# untitled.net
KiCad netlist of a schematic drawn in EAGLE
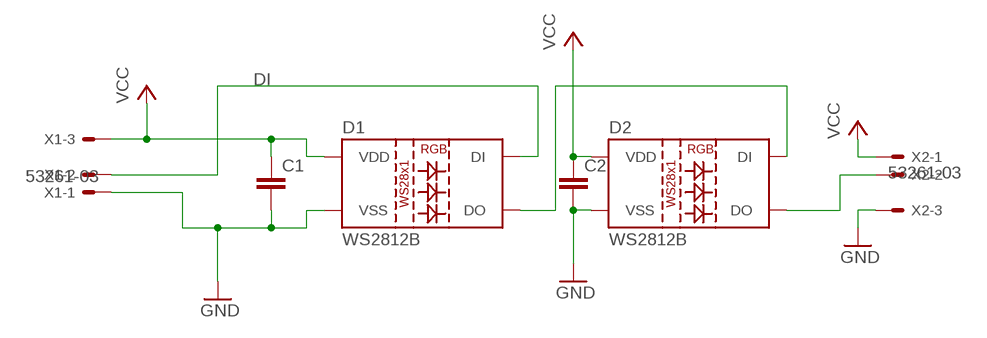
[diagram p0: schematic, sheet 1]

(export (version "E")
  (design (tool "Eeschema 10.0.6"))
  (components
    (comp (ref "C1")
      (value "C-EUC0603")
      (footprint "eagle-import:C0603")
      (libsource (lib "eagle-import") (part "C-EUC0603"))
    )
    (comp (ref "C2")
      (value "C-EUC0603")
      (footprint "eagle-import:C0603")
      (libsource (lib "eagle-import") (part "C-EUC0603"))
    )
    (comp (ref "D1")
      (value "WS2812B")
      (footprint "eagle-import:WS2812B")
      (libsource (lib "eagle-import") (part "WS2812B"))
    )
    (comp (ref "D2")
      (value "WS2812B")
      (footprint "eagle-import:WS2812B")
      (libsource (lib "eagle-import") (part "WS2812B"))
    )
    (comp (ref "X1")
      (value "53261-03")
      (footprint "eagle-import:53261-03")
      (fields (field (name "MF") "MOLEX") (field (name "MPN") "53261-0390"))
      (libsource (lib "eagle-import") (part "53?-03261"))
    )
    (comp (ref "X2")
      (value "53261-03")
      (footprint "eagle-import:53261-03")
      (fields (field (name "MF") "MOLEX") (field (name "MPN") "53261-0390"))
      (libsource (lib "eagle-import") (part "53?-03261"))
    )
  )
  (nets
    (net (code "1") (name "/DI") (class "Default")
      (node (ref "D1") (pin "4") (pinfunction "DI_4") (pintype "bidirectional"))
      (node (ref "X1") (pin "2") (pinfunction "S_2") (pintype "passive"))
    )
    (net (code "2") (name "GND") (class "Default")
      (node (ref "C1") (pin "2") (pinfunction "2_2") (pintype "passive"))
      (node (ref "C2") (pin "2") (pinfunction "2_2") (pintype "passive"))
      (node (ref "D1") (pin "3") (pinfunction "VSS_3") (pintype "bidirectional"))
      (node (ref "D2") (pin "3") (pinfunction "VSS_3") (pintype "bidirectional"))
      (node (ref "X1") (pin "1") (pinfunction "S_1") (pintype "passive"))
      (node (ref "X2") (pin "3") (pinfunction "S_3") (pintype "passive"))
    )
    (net (code "3") (name "Net-(D1-DO)") (class "Default")
      (node (ref "D1") (pin "2") (pinfunction "DO_2") (pintype "bidirectional"))
      (node (ref "D2") (pin "4") (pinfunction "DI_4") (pintype "bidirectional"))
    )
    (net (code "4") (name "Net-(D2-DO)") (class "Default")
      (node (ref "D2") (pin "2") (pinfunction "DO_2") (pintype "bidirectional"))
      (node (ref "X2") (pin "2") (pinfunction "S_2") (pintype "passive"))
    )
    (net (code "5") (name "VCC") (class "Default")
      (node (ref "C1") (pin "1") (pinfunction "1_1") (pintype "passive"))
      (node (ref "C2") (pin "1") (pinfunction "1_1") (pintype "passive"))
      (node (ref "D1") (pin "1") (pinfunction "VDD_1") (pintype "bidirectional"))
      (node (ref "D2") (pin "1") (pinfunction "VDD_1") (pintype "bidirectional"))
      (node (ref "X1") (pin "3") (pinfunction "S_3") (pintype "passive"))
      (node (ref "X2") (pin "1") (pinfunction "S_1") (pintype "passive"))
    )
  )
)
